# battery_cell.net
KiCad netlist of a schematic drawn in Altium Designer
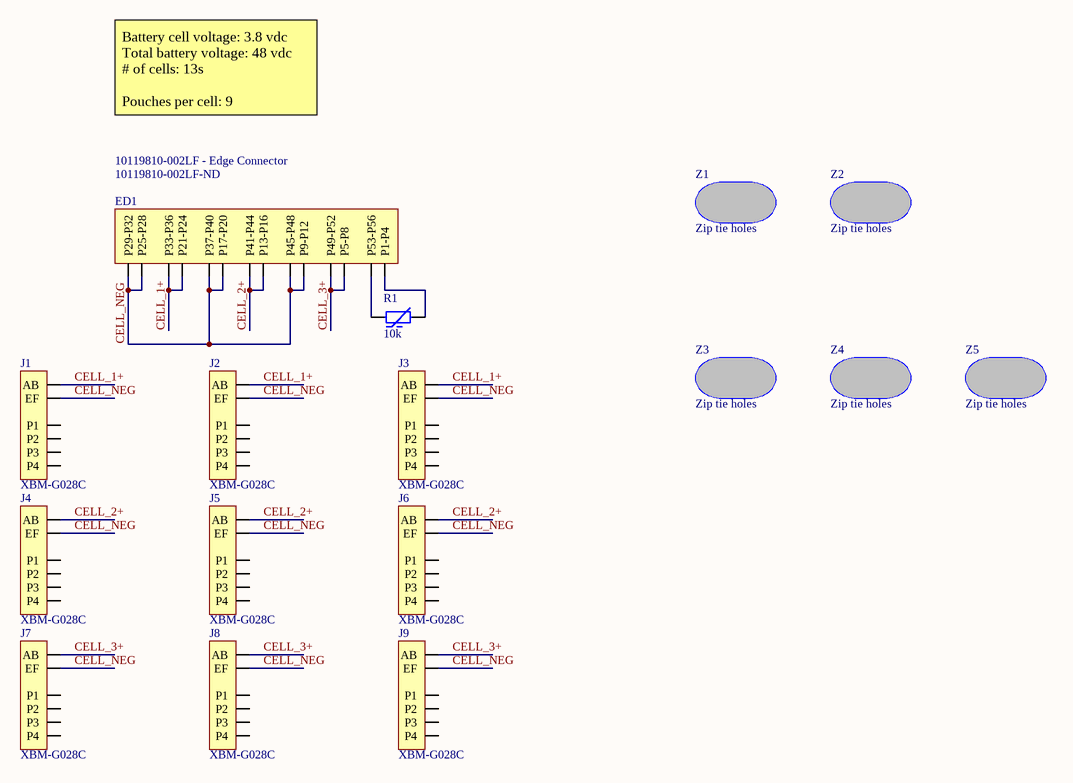
[diagram p0: battery_cell.SchDoc]

(export (version "E")
  (design (tool "Eeschema 10.0.6"))
  (components
    (comp (ref "ED1")
      (value "10119810-002LF - Edge Connector")
      (footprint "10119810-002LF - Edge Connector")
      (fields (field (name "SUPPLIER PART NUMBER 1") "10119810-002LF-ND"))
      (libsource (lib "bms") (part "10119810-002LF - Edge Connector"))
    )
    (comp (ref "J1")
      (value "XBM-G028C")
      (footprint "XBM-G028A")
      (description "28 pos power connector  (0.8X1.6mm pitch)-with post")
      (fields (field (name "MANUFACTURER") "Neoconix"))
      (libsource (lib "bms") (part "XBM-G028C"))
    )
    (comp (ref "J2")
      (value "XBM-G028C")
      (footprint "XBM-G028A")
      (description "28 pos power connector  (0.8X1.6mm pitch)-with post")
      (fields (field (name "MANUFACTURER") "Neoconix"))
      (libsource (lib "bms") (part "XBM-G028C"))
    )
    (comp (ref "J3")
      (value "XBM-G028C")
      (footprint "XBM-G028A")
      (description "28 pos power connector  (0.8X1.6mm pitch)-with post")
      (fields (field (name "MANUFACTURER") "Neoconix"))
      (libsource (lib "bms") (part "XBM-G028C"))
    )
    (comp (ref "J4")
      (value "XBM-G028C")
      (footprint "XBM-G028A")
      (description "28 pos power connector  (0.8X1.6mm pitch)-with post")
      (fields (field (name "MANUFACTURER") "Neoconix"))
      (libsource (lib "bms") (part "XBM-G028C"))
    )
    (comp (ref "J5")
      (value "XBM-G028C")
      (footprint "XBM-G028A")
      (description "28 pos power connector  (0.8X1.6mm pitch)-with post")
      (fields (field (name "MANUFACTURER") "Neoconix"))
      (libsource (lib "bms") (part "XBM-G028C"))
    )
    (comp (ref "J6")
      (value "XBM-G028C")
      (footprint "XBM-G028A")
      (description "28 pos power connector  (0.8X1.6mm pitch)-with post")
      (fields (field (name "MANUFACTURER") "Neoconix"))
      (libsource (lib "bms") (part "XBM-G028C"))
    )
    (comp (ref "J7")
      (value "XBM-G028C")
      (footprint "XBM-G028A")
      (description "28 pos power connector  (0.8X1.6mm pitch)-with post")
      (fields (field (name "MANUFACTURER") "Neoconix"))
      (libsource (lib "bms") (part "XBM-G028C"))
    )
    (comp (ref "J8")
      (value "XBM-G028C")
      (footprint "XBM-G028A")
      (description "28 pos power connector  (0.8X1.6mm pitch)-with post")
      (fields (field (name "MANUFACTURER") "Neoconix"))
      (libsource (lib "bms") (part "XBM-G028C"))
    )
    (comp (ref "J9")
      (value "XBM-G028C")
      (footprint "XBM-G028A")
      (description "28 pos power connector  (0.8X1.6mm pitch)-with post")
      (fields (field (name "MANUFACTURER") "Neoconix"))
      (libsource (lib "bms") (part "XBM-G028C"))
    )
    (comp (ref "R1")
      (value "10k")
      (footprint "NTC 0603_1608")
      (description "THERMISTOR NTC 10KOHM 3610K 0603")
      (fields
        (field (name "PART NUMBER") "NTCS0603E3103FMT")
        (field (name "MANUFACTURER") "Vishay BC Components")
      )
      (libsource (lib "Celestial Altium Library - altium_library") (part "Thermistor"))
    )
    (comp (ref "Z1")
      (value "Zip tie holes")
      (footprint "ZIP_TIE_HOLE")
      (libsource (lib "bms") (part "ZIP_TIE_HOLE"))
    )
    (comp (ref "Z2")
      (value "Zip tie holes")
      (footprint "ZIP_TIE_HOLE")
      (libsource (lib "bms") (part "ZIP_TIE_HOLE"))
    )
    (comp (ref "Z3")
      (value "Zip tie holes")
      (footprint "ZIP_TIE_HOLE")
      (libsource (lib "bms") (part "ZIP_TIE_HOLE"))
    )
    (comp (ref "Z4")
      (value "Zip tie holes")
      (footprint "ZIP_TIE_HOLE")
      (libsource (lib "bms") (part "ZIP_TIE_HOLE"))
    )
    (comp (ref "Z5")
      (value "Zip tie holes")
      (footprint "ZIP_TIE_HOLE")
      (libsource (lib "bms") (part "ZIP_TIE_HOLE"))
    )
  )
  (nets
    (net (code "1") (name "/CELL_1+") (class "Default")
      (node (ref "ED1") (pin "P21-P24") (pinfunction "P21-P24_P21-P24") (pintype "power_in"))
      (node (ref "ED1") (pin "P33-P36") (pinfunction "P33-P36_P33-P36") (pintype "power_in"))
      (node (ref "J1") (pin "AB") (pinfunction "AB_AB") (pintype "power_in"))
      (node (ref "J2") (pin "AB") (pinfunction "AB_AB") (pintype "power_in"))
      (node (ref "J3") (pin "AB") (pinfunction "AB_AB") (pintype "power_in"))
    )
    (net (code "2") (name "/CELL_2+") (class "Default")
      (node (ref "ED1") (pin "P13-P16") (pinfunction "P13-P16_P13-P16") (pintype "power_in"))
      (node (ref "ED1") (pin "P41-P44") (pinfunction "P41-P44_P41-P44") (pintype "power_in"))
      (node (ref "J4") (pin "AB") (pinfunction "AB_AB") (pintype "power_in"))
      (node (ref "J5") (pin "AB") (pinfunction "AB_AB") (pintype "power_in"))
      (node (ref "J6") (pin "AB") (pinfunction "AB_AB") (pintype "power_in"))
    )
    (net (code "3") (name "/CELL_3+") (class "Default")
      (node (ref "ED1") (pin "P49-P52") (pinfunction "P49-P52_P49-P52") (pintype "power_in"))
      (node (ref "ED1") (pin "P5-P8") (pinfunction "P5-P8_P5-P8") (pintype "power_in"))
      (node (ref "J7") (pin "AB") (pinfunction "AB_AB") (pintype "power_in"))
      (node (ref "J8") (pin "AB") (pinfunction "AB_AB") (pintype "power_in"))
      (node (ref "J9") (pin "AB") (pinfunction "AB_AB") (pintype "power_in"))
    )
    (net (code "4") (name "/CELL_NEG") (class "Default")
      (node (ref "ED1") (pin "P17-P20") (pinfunction "P17-P20_P17-P20") (pintype "power_in"))
      (node (ref "ED1") (pin "P25-P28") (pinfunction "P25-P28_P25-P28") (pintype "power_in"))
      (node (ref "ED1") (pin "P29-P32") (pinfunction "P29-P32_P29-P32") (pintype "power_in"))
      (node (ref "ED1") (pin "P37-P40") (pinfunction "P37-P40_P37-P40") (pintype "power_in"))
      (node (ref "ED1") (pin "P45-P48") (pinfunction "P45-P48_P45-P48") (pintype "power_in"))
      (node (ref "ED1") (pin "P9-P12") (pinfunction "P9-P12_P9-P12") (pintype "power_in"))
      (node (ref "J1") (pin "EF") (pinfunction "EF_EF") (pintype "power_in"))
      (node (ref "J2") (pin "EF") (pinfunction "EF_EF") (pintype "power_in"))
      (node (ref "J3") (pin "EF") (pinfunction "EF_EF") (pintype "power_in"))
      (node (ref "J4") (pin "EF") (pinfunction "EF_EF") (pintype "power_in"))
      (node (ref "J5") (pin "EF") (pinfunction "EF_EF") (pintype "power_in"))
      (node (ref "J6") (pin "EF") (pinfunction "EF_EF") (pintype "power_in"))
      (node (ref "J7") (pin "EF") (pinfunction "EF_EF") (pintype "power_in"))
      (node (ref "J8") (pin "EF") (pinfunction "EF_EF") (pintype "power_in"))
      (node (ref "J9") (pin "EF") (pinfunction "EF_EF") (pintype "power_in"))
    )
    (net (code "5") (name "Net-(ED1-PadP1-P4)") (class "Default")
      (node (ref "ED1") (pin "P1-P4") (pinfunction "P1-P4_P1-P4") (pintype "power_in"))
      (node (ref "R1") (pin "2") (pinfunction "2_2") (pintype "passive"))
    )
    (net (code "6") (name "Net-(ED1-PadP53-P56)") (class "Default")
      (node (ref "ED1") (pin "P53-P56") (pinfunction "P53-P56_P53-P56") (pintype "power_in"))
      (node (ref "R1") (pin "1") (pinfunction "1_1") (pintype "passive"))
    )
    (net (code "7") (name "unconnected-(J1-PadP1)") (class "Default")
      (node (ref "J1") (pin "P1") (pinfunction "P1_P1") (pintype "passive"))
    )
    (net (code "8") (name "unconnected-(J1-PadP2)") (class "Default")
      (node (ref "J1") (pin "P2") (pinfunction "P2_P2") (pintype "passive"))
    )
    (net (code "9") (name "unconnected-(J1-PadP3)") (class "Default")
      (node (ref "J1") (pin "P3") (pinfunction "P3_P3") (pintype "passive"))
    )
    (net (code "10") (name "unconnected-(J1-PadP4)") (class "Default")
      (node (ref "J1") (pin "P4") (pinfunction "P4_P4") (pintype "passive"))
    )
    (net (code "11") (name "unconnected-(J2-PadP1)") (class "Default")
      (node (ref "J2") (pin "P1") (pinfunction "P1_P1") (pintype "passive"))
    )
    (net (code "12") (name "unconnected-(J2-PadP2)") (class "Default")
      (node (ref "J2") (pin "P2") (pinfunction "P2_P2") (pintype "passive"))
    )
    (net (code "13") (name "unconnected-(J2-PadP3)") (class "Default")
      (node (ref "J2") (pin "P3") (pinfunction "P3_P3") (pintype "passive"))
    )
    (net (code "14") (name "unconnected-(J2-PadP4)") (class "Default")
      (node (ref "J2") (pin "P4") (pinfunction "P4_P4") (pintype "passive"))
    )
    (net (code "15") (name "unconnected-(J3-PadP1)") (class "Default")
      (node (ref "J3") (pin "P1") (pinfunction "P1_P1") (pintype "passive"))
    )
    (net (code "16") (name "unconnected-(J3-PadP2)") (class "Default")
      (node (ref "J3") (pin "P2") (pinfunction "P2_P2") (pintype "passive"))
    )
    (net (code "17") (name "unconnected-(J3-PadP3)") (class "Default")
      (node (ref "J3") (pin "P3") (pinfunction "P3_P3") (pintype "passive"))
    )
    (net (code "18") (name "unconnected-(J3-PadP4)") (class "Default")
      (node (ref "J3") (pin "P4") (pinfunction "P4_P4") (pintype "passive"))
    )
    (net (code "19") (name "unconnected-(J4-PadP1)") (class "Default")
      (node (ref "J4") (pin "P1") (pinfunction "P1_P1") (pintype "passive"))
    )
    (net (code "20") (name "unconnected-(J4-PadP2)") (class "Default")
      (node (ref "J4") (pin "P2") (pinfunction "P2_P2") (pintype "passive"))
    )
    (net (code "21") (name "unconnected-(J4-PadP3)") (class "Default")
      (node (ref "J4") (pin "P3") (pinfunction "P3_P3") (pintype "passive"))
    )
    (net (code "22") (name "unconnected-(J4-PadP4)") (class "Default")
      (node (ref "J4") (pin "P4") (pinfunction "P4_P4") (pintype "passive"))
    )
    (net (code "23") (name "unconnected-(J5-PadP1)") (class "Default")
      (node (ref "J5") (pin "P1") (pinfunction "P1_P1") (pintype "passive"))
    )
    (net (code "24") (name "unconnected-(J5-PadP2)") (class "Default")
      (node (ref "J5") (pin "P2") (pinfunction "P2_P2") (pintype "passive"))
    )
    (net (code "25") (name "unconnected-(J5-PadP3)") (class "Default")
      (node (ref "J5") (pin "P3") (pinfunction "P3_P3") (pintype "passive"))
    )
    (net (code "26") (name "unconnected-(J5-PadP4)") (class "Default")
      (node (ref "J5") (pin "P4") (pinfunction "P4_P4") (pintype "passive"))
    )
    (net (code "27") (name "unconnected-(J6-PadP1)") (class "Default")
      (node (ref "J6") (pin "P1") (pinfunction "P1_P1") (pintype "passive"))
    )
    (net (code "28") (name "unconnected-(J6-PadP2)") (class "Default")
      (node (ref "J6") (pin "P2") (pinfunction "P2_P2") (pintype "passive"))
    )
    (net (code "29") (name "unconnected-(J6-PadP3)") (class "Default")
      (node (ref "J6") (pin "P3") (pinfunction "P3_P3") (pintype "passive"))
    )
    (net (code "30") (name "unconnected-(J6-PadP4)") (class "Default")
      (node (ref "J6") (pin "P4") (pinfunction "P4_P4") (pintype "passive"))
    )
    (net (code "31") (name "unconnected-(J7-PadP1)") (class "Default")
      (node (ref "J7") (pin "P1") (pinfunction "P1_P1") (pintype "passive"))
    )
    (net (code "32") (name "unconnected-(J7-PadP2)") (class "Default")
      (node (ref "J7") (pin "P2") (pinfunction "P2_P2") (pintype "passive"))
    )
    (net (code "33") (name "unconnected-(J7-PadP3)") (class "Default")
      (node (ref "J7") (pin "P3") (pinfunction "P3_P3") (pintype "passive"))
    )
    (net (code "34") (name "unconnected-(J7-PadP4)") (class "Default")
      (node (ref "J7") (pin "P4") (pinfunction "P4_P4") (pintype "passive"))
    )
    (net (code "35") (name "unconnected-(J8-PadP1)") (class "Default")
      (node (ref "J8") (pin "P1") (pinfunction "P1_P1") (pintype "passive"))
    )
    (net (code "36") (name "unconnected-(J8-PadP2)") (class "Default")
      (node (ref "J8") (pin "P2") (pinfunction "P2_P2") (pintype "passive"))
    )
    (net (code "37") (name "unconnected-(J8-PadP3)") (class "Default")
      (node (ref "J8") (pin "P3") (pinfunction "P3_P3") (pintype "passive"))
    )
    (net (code "38") (name "unconnected-(J8-PadP4)") (class "Default")
      (node (ref "J8") (pin "P4") (pinfunction "P4_P4") (pintype "passive"))
    )
    (net (code "39") (name "unconnected-(J9-PadP1)") (class "Default")
      (node (ref "J9") (pin "P1") (pinfunction "P1_P1") (pintype "passive"))
    )
    (net (code "40") (name "unconnected-(J9-PadP2)") (class "Default")
      (node (ref "J9") (pin "P2") (pinfunction "P2_P2") (pintype "passive"))
    )
    (net (code "41") (name "unconnected-(J9-PadP3)") (class "Default")
      (node (ref "J9") (pin "P3") (pinfunction "P3_P3") (pintype "passive"))
    )
    (net (code "42") (name "unconnected-(J9-PadP4)") (class "Default")
      (node (ref "J9") (pin "P4") (pinfunction "P4_P4") (pintype "passive"))
    )
  )
)
